# Connect.net
KiCad netlist of a schematic drawn in Altium Designer
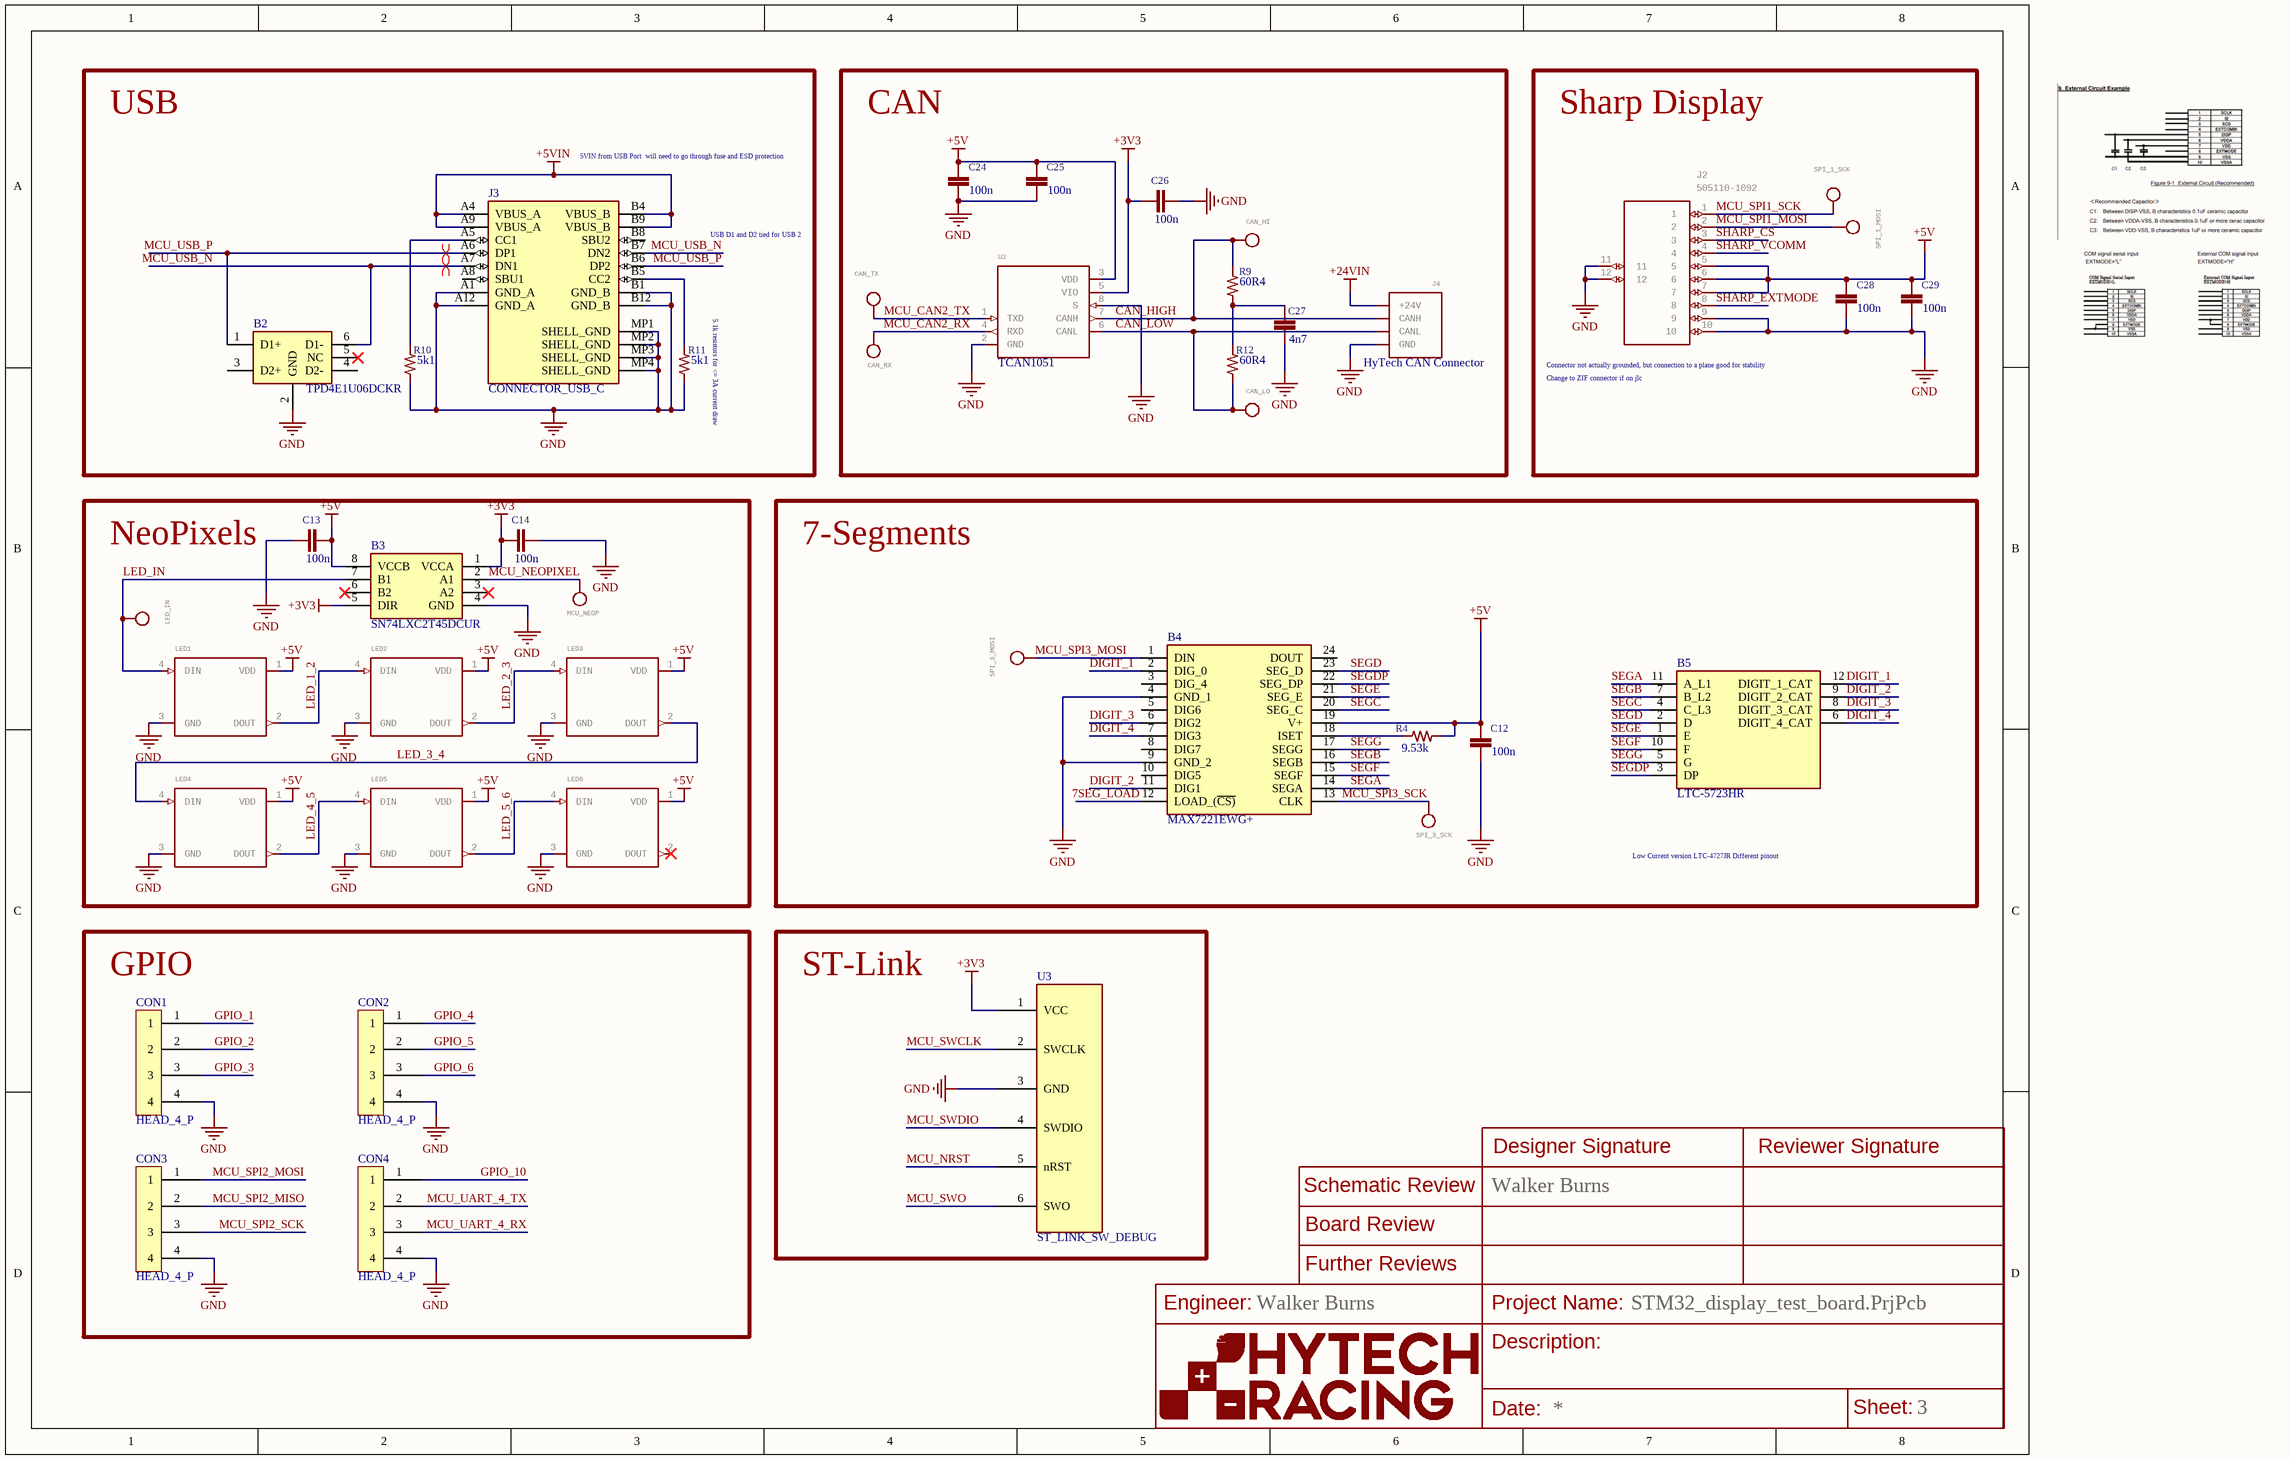
[diagram p0: Connect.SchDoc]

(export (version "E")
  (design (tool "Eeschema 10.0.6"))
  (components
    (comp (ref "B2")
      (value "TPD4E1U06DCKR")
      (footprint "SC-70-6")
      (description "Quad-Channel High-Speed ESD Protection Device")
      (fields (field (name "MOUSER PART NUMBER") "595-TPD4E1U06DCKR"))
      (libsource (lib "HyTechDevices") (part "TPD4E1U06DCKR"))
    )
    (comp (ref "B3")
      (value "SN74LXC2T45DCUR")
      (footprint "VSSOP-8")
      (fields (field (name "MOUSER PART NUMBER") "595-SN74LXC2T45DCUR"))
      (libsource (lib "HyTechDevices") (part "LEVEL_SHIFTER_3V3_TO_5V"))
    )
    (comp (ref "B4")
      (value "MAX7221EWG+")
      (footprint "SOIC-24")
      (description "MAX7221EWG+, LED Display Driver, 8-Digits 64-Segments, 4  5.5 V, 24-Pin SOIC W")
      (fields (field (name "MOUSER PART NUMBER") "700-MAX7221EWG"))
      (libsource (lib "HyTechDevices") (part "MAX7221EWG+"))
    )
    (comp (ref "B5")
      (value "LTC-5723HR")
      (footprint "7SEGMENT_DISP_12_P_TH")
      (description "LED Displays & Accessories 4 Digit, Red Normal Current, Common  Cathode")
      (fields
        (field (name "MOUSER PART NUMBER") "859-LTC-4627JR")
        (field (name "MANUFACTURER_PART_NUMBER") "LTC-4627JR")
      )
      (libsource (lib "HyTechDevices") (part "LED_7_SEGMENT_4_DIGIT"))
    )
    (comp (ref "C12")
      (value "100n")
      (footprint "0402_CAP")
      (fields
        (field (name "MANUFACTURER") "Yageo")
        (field (name "MPN") "CC0603KRX7R0BB104")
        (field (name "TOLERANCE") "10%")
      )
      (libsource (lib "HyTechDevices") (part "CAPACITOR_?_*0402"))
    )
    (comp (ref "C13")
      (value "100n")
      (footprint "0402_CAP")
      (fields
        (field (name "MANUFACTURER") "Yageo")
        (field (name "MPN") "CC0603KRX7R0BB104")
        (field (name "TOLERANCE") "10%")
      )
      (libsource (lib "") (part "CAPACITOR_?_*0402_1"))
    )
    (comp (ref "C14")
      (value "100n")
      (footprint "0402_CAP")
      (fields
        (field (name "MANUFACTURER") "Yageo")
        (field (name "MPN") "CC0603KRX7R0BB104")
        (field (name "TOLERANCE") "10%")
      )
      (libsource (lib "") (part "CAPACITOR_?_*0402_1"))
    )
    (comp (ref "C24")
      (value "100n")
      (footprint "0402_CAP")
      (fields
        (field (name "MANUFACTURER") "Yageo")
        (field (name "MPN") "CC0603KRX7R0BB104")
        (field (name "TOLERANCE") "10%")
      )
      (libsource (lib "HyTechDevices") (part "CAPACITOR_?_*0402"))
    )
    (comp (ref "C25")
      (value "100n")
      (footprint "0402_CAP")
      (fields
        (field (name "MANUFACTURER") "Yageo")
        (field (name "MPN") "CC0603KRX7R0BB104")
        (field (name "TOLERANCE") "10%")
      )
      (libsource (lib "HyTechDevices") (part "CAPACITOR_?_*0402"))
    )
    (comp (ref "C26")
      (value "100n")
      (footprint "0402_CAP")
      (fields
        (field (name "MANUFACTURER") "Yageo")
        (field (name "MPN") "CC0603KRX7R0BB104")
        (field (name "TOLERANCE") "10%")
      )
      (libsource (lib "") (part "CAPACITOR_?_*0402_1"))
    )
    (comp (ref "C27")
      (value "4n7")
      (footprint "0603-CAP")
      (fields
        (field (name "MANUFACTURER") "Yageo")
        (field (name "MPN") "CC0603KRX7R0BB104")
        (field (name "TOLERANCE") "10%")
      )
      (libsource (lib "HyTechDevices") (part "CAPACITOR_?_*0603"))
    )
    (comp (ref "C28")
      (value "100n")
      (footprint "0402_CAP")
      (fields
        (field (name "MANUFACTURER") "Yageo")
        (field (name "MPN") "CC0603KRX7R0BB104")
        (field (name "TOLERANCE") "10%")
      )
      (libsource (lib "HyTechDevices") (part "CAPACITOR_?_*0402"))
    )
    (comp (ref "C29")
      (value "100n")
      (footprint "0402_CAP")
      (fields
        (field (name "MANUFACTURER") "Yageo")
        (field (name "MPN") "CC0603KRX7R0BB104")
        (field (name "TOLERANCE") "10%")
      )
      (libsource (lib "HyTechDevices") (part "CAPACITOR_?_*0402"))
    )
    (comp (ref "CAN_HI")
      (value "Test Point for Probing")
      (footprint "5015")
      (fields (field (name "MANUFACTURER") "Keystone Electronics") (field (name "MPN") "5015"))
      (libsource (lib "HyTechDevices") (part "TEST_POINT"))
    )
    (comp (ref "CAN_LO")
      (value "Test Point for Probing")
      (footprint "5015")
      (fields (field (name "MANUFACTURER") "Keystone Electronics") (field (name "MPN") "5015"))
      (libsource (lib "HyTechDevices") (part "TEST_POINT"))
    )
    (comp (ref "CAN_RX")
      (value "Test Point for Probing")
      (footprint "5015")
      (fields (field (name "MANUFACTURER") "Keystone Electronics") (field (name "MPN") "5015"))
      (libsource (lib "HyTechDevices") (part "TEST_POINT"))
    )
    (comp (ref "CAN_TX")
      (value "Test Point for Probing")
      (footprint "5015")
      (fields (field (name "MANUFACTURER") "Keystone Electronics") (field (name "MPN") "5015"))
      (libsource (lib "HyTechDevices") (part "TEST_POINT"))
    )
    (comp (ref "CON1")
      (value "HEAD_4_P")
      (footprint "1X04")
      (description "4 Pin Standard Header")
      (libsource (lib "HyTechDevices") (part "CONNECTOR_HEADER_4"))
    )
    (comp (ref "CON2")
      (value "HEAD_4_P")
      (footprint "1X04")
      (description "4 Pin Standard Header")
      (libsource (lib "HyTechDevices") (part "CONNECTOR_HEADER_4"))
    )
    (comp (ref "CON3")
      (value "HEAD_4_P")
      (footprint "1X04")
      (description "4 Pin Standard Header")
      (libsource (lib "HyTechDevices") (part "CONNECTOR_HEADER_4"))
    )
    (comp (ref "CON4")
      (value "HEAD_4_P")
      (footprint "1X04")
      (description "4 Pin Standard Header")
      (libsource (lib "HyTechDevices") (part "CONNECTOR_HEADER_4"))
    )
    (comp (ref "FRAME3")
      (value "HyTech Racing Frame (ANSI Size A)  Prints on US Letter Landscape 8.5\" by 11\"   Fill Engineer/Description Fields with Text using the following settings:  Size: 0.1  Ratio: 8%  Line Distance: 50%  Font: Proportional  Layer: 94 Symbol")
      (fields (field (name "LIBRARYNAME") "HyTechFrames"))
      (libsource (lib "HyTechFrames") (part "FRAME"))
    )
    (comp (ref "J2")
      (value "505110-1092")
      (footprint "MOLEX_FPC_CLAMSHELL_10")
      (fields (field (name "MOUSER_PART_NUMBER") "538-505110-1092"))
      (libsource (lib "HyTechDevices") (part "CONNECTOR-10_MOLEX_FPC_CLAMSHELL"))
    )
    (comp (ref "J3")
      (value "CONNECTOR_USB_C")
      (footprint "USB4110GFA")
      (description "USB4110-GF-A\r\nGCT USB C Connector")
      (fields (field (name "MF") "Valcon") (field (name "MP") "CSP-USC16-TR"))
      (libsource (lib "HyTechDevices") (part "CONNECTOR_USB_C"))
    )
    (comp (ref "J4")
      (value "HyTech CAN Connector")
      (footprint "MOLEX_MICROFIT_SMD_RIGHTANGLE_04_DUAL")
      (fields (field (name "MANUFACTURER") "Molex") (field (name "MPN") "0430450411"))
      (libsource (lib "HyTechDevices") (part "CONNECTOR-CAN_?_*μF_S_RA"))
    )
    (comp (ref "LED1")
      (value "IN-PI55QATPRPGPBPW-40  Neopixel RGBW LED  Datasheet")
      (footprint "NEOPIXEL")
      (fields (field (name "MANUFACTURER") "Inolux") (field (name "MPN") "IN-PI55QATPRPGPBPW-40"))
      (libsource (lib "HyTechDevices") (part "NEOPIXEL_*IN-PI55QATPRPGPBPW-40"))
    )
    (comp (ref "LED2")
      (value "IN-PI55QATPRPGPBPW-40  Neopixel RGBW LED  Datasheet")
      (footprint "NEOPIXEL")
      (fields (field (name "MANUFACTURER") "Inolux") (field (name "MPN") "IN-PI55QATPRPGPBPW-40"))
      (libsource (lib "HyTechDevices") (part "NEOPIXEL_*IN-PI55QATPRPGPBPW-40"))
    )
    (comp (ref "LED3")
      (value "IN-PI55QATPRPGPBPW-40  Neopixel RGBW LED  Datasheet")
      (footprint "NEOPIXEL")
      (fields (field (name "MANUFACTURER") "Inolux") (field (name "MPN") "IN-PI55QATPRPGPBPW-40"))
      (libsource (lib "HyTechDevices") (part "NEOPIXEL_*IN-PI55QATPRPGPBPW-40"))
    )
    (comp (ref "LED4")
      (value "IN-PI55QATPRPGPBPW-40  Neopixel RGBW LED  Datasheet")
      (footprint "NEOPIXEL")
      (fields (field (name "MANUFACTURER") "Inolux") (field (name "MPN") "IN-PI55QATPRPGPBPW-40"))
      (libsource (lib "HyTechDevices") (part "NEOPIXEL_*IN-PI55QATPRPGPBPW-40"))
    )
    (comp (ref "LED5")
      (value "IN-PI55QATPRPGPBPW-40  Neopixel RGBW LED  Datasheet")
      (footprint "NEOPIXEL")
      (fields (field (name "MANUFACTURER") "Inolux") (field (name "MPN") "IN-PI55QATPRPGPBPW-40"))
      (libsource (lib "HyTechDevices") (part "NEOPIXEL_*IN-PI55QATPRPGPBPW-40"))
    )
    (comp (ref "LED6")
      (value "IN-PI55QATPRPGPBPW-40  Neopixel RGBW LED  Datasheet")
      (footprint "NEOPIXEL")
      (fields (field (name "MANUFACTURER") "Inolux") (field (name "MPN") "IN-PI55QATPRPGPBPW-40"))
      (libsource (lib "HyTechDevices") (part "NEOPIXEL_*IN-PI55QATPRPGPBPW-40"))
    )
    (comp (ref "LED_IN")
      (value "Test Point for Probing")
      (footprint "5015")
      (fields (field (name "MANUFACTURER") "Keystone Electronics") (field (name "MPN") "5015"))
      (libsource (lib "HyTechDevices") (part "TEST_POINT"))
    )
    (comp (ref "MCU_NEOP")
      (value "Test Point for Probing")
      (footprint "5015")
      (fields (field (name "MANUFACTURER") "Keystone Electronics") (field (name "MPN") "5015"))
      (libsource (lib "HyTechDevices") (part "TEST_POINT"))
    )
    (comp (ref "R4")
      (value "9.53k")
      (footprint "0603-RES")
      (fields
        (field (name "MANUFACTURER") "Yageo")
        (field (name "MPN") "RC0603FR-070RL")
        (field (name "POWER") "0.1W")
      )
      (libsource (lib "") (part "RESISTOR_?_*0603_1"))
    )
    (comp (ref "R9")
      (value "60R4")
      (footprint "0603-RES")
      (fields
        (field (name "MANUFACTURER") "Yageo")
        (field (name "MPN") "RC0603FR-070RL")
        (field (name "POWER") "0.1W")
      )
      (libsource (lib "HyTechDevices") (part "RESISTOR_?_*0603"))
    )
    (comp (ref "R10")
      (value "5k1")
      (footprint "0603-RES")
      (fields
        (field (name "MANUFACTURER") "Yageo")
        (field (name "MPN") "RC0603FR-070RL")
        (field (name "POWER") "0.1W")
      )
      (libsource (lib "HyTechDevices") (part "RESISTOR_?_*0603"))
    )
    (comp (ref "R11")
      (value "5k1")
      (footprint "0603-RES")
      (fields
        (field (name "MANUFACTURER") "Yageo")
        (field (name "MPN") "RC0603FR-070RL")
        (field (name "POWER") "0.1W")
      )
      (libsource (lib "HyTechDevices") (part "RESISTOR_?_*0603"))
    )
    (comp (ref "R12")
      (value "60R4")
      (footprint "0603-RES")
      (fields
        (field (name "MANUFACTURER") "Yageo")
        (field (name "MPN") "RC0603FR-070RL")
        (field (name "POWER") "0.1W")
      )
      (libsource (lib "HyTechDevices") (part "RESISTOR_?_*0603"))
    )
    (comp (ref "SPI_1_MOSI")
      (value "Test Point for Probing")
      (footprint "5015")
      (fields (field (name "MANUFACTURER") "Keystone Electronics") (field (name "MPN") "5015"))
      (libsource (lib "HyTechDevices") (part "TEST_POINT"))
    )
    (comp (ref "SPI_1_SCK")
      (value "Test Point for Probing")
      (footprint "5015")
      (fields (field (name "MANUFACTURER") "Keystone Electronics") (field (name "MPN") "5015"))
      (libsource (lib "HyTechDevices") (part "TEST_POINT"))
    )
    (comp (ref "SPI_3_MOSI")
      (value "Test Point for Probing")
      (footprint "5015")
      (fields (field (name "MANUFACTURER") "Keystone Electronics") (field (name "MPN") "5015"))
      (libsource (lib "HyTechDevices") (part "TEST_POINT"))
    )
    (comp (ref "SPI_3_SCK")
      (value "Test Point for Probing")
      (footprint "5015")
      (fields (field (name "MANUFACTURER") "Keystone Electronics") (field (name "MPN") "5015"))
      (libsource (lib "HyTechDevices") (part "TEST_POINT"))
    )
    (comp (ref "U2")
      (value "TCAN1051")
      (footprint "SOIC-08(NARROW,0-15\")")
      (fields (field (name "MANUFACTURER") "Texas Instruments") (field (name "MPN") "TCAN1051HGVDRQ1"))
      (libsource (lib "HyTechDevices") (part "TCAN1051*V-Q1"))
    )
    (comp (ref "U3")
      (value "ST_LINK_SW_DEBUG")
      (footprint "HEADER_6_P")
      (libsource (lib "HyTechDevices") (part "CONNECTOR_ST_LINK"))
    )
  )
  (nets
    (net (code "1") (name "+3V3") (class "Default")
      (node (ref "B3") (pin "1") (pinfunction "VCCA_1") (pintype "passive"))
      (node (ref "B3") (pin "5") (pinfunction "DIR_5") (pintype "passive"))
      (node (ref "C14") (pin "2") (pinfunction "2_2") (pintype "passive"))
      (node (ref "C26") (pin "2") (pinfunction "2_2") (pintype "passive"))
      (node (ref "U2") (pin "5") (pinfunction "VIO_5") (pintype "power_in"))
      (node (ref "U3") (pin "1") (pinfunction "VCC_1") (pintype "passive"))
    )
    (net (code "2") (name "+5V") (class "Default")
      (node (ref "B3") (pin "8") (pinfunction "VCCB_8") (pintype "passive"))
      (node (ref "B4") (pin "19") (pinfunction "V+_19") (pintype "passive"))
      (node (ref "C12") (pin "2") (pinfunction "2_2") (pintype "passive"))
      (node (ref "C13") (pin "1") (pinfunction "1_1") (pintype "passive"))
      (node (ref "C24") (pin "2") (pinfunction "2_2") (pintype "passive"))
      (node (ref "C25") (pin "2") (pinfunction "2_2") (pintype "passive"))
      (node (ref "C28") (pin "2") (pinfunction "2_2") (pintype "passive"))
      (node (ref "C29") (pin "2") (pinfunction "2_2") (pintype "passive"))
      (node (ref "J2") (pin "5") (pinfunction "5_5") (pintype "bidirectional"))
      (node (ref "J2") (pin "6") (pinfunction "6_6") (pintype "bidirectional"))
      (node (ref "J2") (pin "7") (pinfunction "7_7") (pintype "bidirectional"))
      (node (ref "LED1") (pin "1") (pinfunction "VDD_1") (pintype "power_in"))
      (node (ref "LED2") (pin "1") (pinfunction "VDD_1") (pintype "power_in"))
      (node (ref "LED3") (pin "1") (pinfunction "VDD_1") (pintype "power_in"))
      (node (ref "LED4") (pin "1") (pinfunction "VDD_1") (pintype "power_in"))
      (node (ref "LED5") (pin "1") (pinfunction "VDD_1") (pintype "power_in"))
      (node (ref "LED6") (pin "1") (pinfunction "VDD_1") (pintype "power_in"))
      (node (ref "R4") (pin "2") (pinfunction "2_2") (pintype "passive"))
      (node (ref "U2") (pin "3") (pinfunction "VDD_3") (pintype "power_in"))
    )
    (net (code "3") (name "+5VIN") (class "Default")
      (node (ref "J3") (pin "A4") (pinfunction "VBUS_A_A4") (pintype "power_in"))
      (node (ref "J3") (pin "A9") (pinfunction "VBUS_A_A9") (pintype "power_in"))
      (node (ref "J3") (pin "B4") (pinfunction "VBUS_B_B4") (pintype "power_in"))
      (node (ref "J3") (pin "B9") (pinfunction "VBUS_B_B9") (pintype "power_in"))
    )
    (net (code "4") (name "+24VIN") (class "Default")
      (node (ref "J4") (pin "1") (pinfunction "+24V_1") (pintype "power_in"))
    )
    (net (code "5") (name "/7SEG_LOAD") (class "Default")
      (node (ref "B4") (pin "12") (pinfunction "LOAD_(~{CS)}_12") (pintype "passive"))
    )
    (net (code "6") (name "/CAN_HIGH") (class "Default")
      (node (ref "CAN_HI") (pin "1") (pinfunction "1_1") (pintype "passive"))
      (node (ref "J4") (pin "4") (pinfunction "CANH_4") (pintype "bidirectional"))
      (node (ref "R9") (pin "1") (pinfunction "1_1") (pintype "passive"))
      (node (ref "U2") (pin "7") (pinfunction "CANH_7") (pintype "output"))
    )
    (net (code "7") (name "/CAN_LOW") (class "Default")
      (node (ref "CAN_LO") (pin "1") (pinfunction "1_1") (pintype "passive"))
      (node (ref "J4") (pin "3") (pinfunction "CANL_3") (pintype "bidirectional"))
      (node (ref "R12") (pin "2") (pinfunction "2_2") (pintype "passive"))
      (node (ref "U2") (pin "6") (pinfunction "CANL_6") (pintype "bidirectional"))
    )
    (net (code "8") (name "/DIGIT_1") (class "Default")
      (node (ref "B4") (pin "2") (pinfunction "DIG_0_2") (pintype "passive"))
      (node (ref "B5") (pin "12") (pinfunction "DIGIT_1_CAT_12") (pintype "passive"))
    )
    (net (code "9") (name "/DIGIT_2") (class "Default")
      (node (ref "B4") (pin "11") (pinfunction "DIG1_11") (pintype "passive"))
      (node (ref "B5") (pin "9") (pinfunction "DIGIT_2_CAT_9") (pintype "passive"))
    )
    (net (code "10") (name "/DIGIT_3") (class "Default")
      (node (ref "B4") (pin "6") (pinfunction "DIG2_6") (pintype "passive"))
      (node (ref "B5") (pin "8") (pinfunction "DIGIT_3_CAT_8") (pintype "passive"))
    )
    (net (code "11") (name "/DIGIT_4") (class "Default")
      (node (ref "B4") (pin "7") (pinfunction "DIG3_7") (pintype "passive"))
      (node (ref "B5") (pin "6") (pinfunction "DIGIT_4_CAT_6") (pintype "passive"))
    )
    (net (code "12") (name "/GPIO_1") (class "Default")
      (node (ref "CON1") (pin "1") (pinfunction "1_1") (pintype "passive"))
    )
    (net (code "13") (name "/GPIO_2") (class "Default")
      (node (ref "CON1") (pin "2") (pinfunction "2_2") (pintype "passive"))
    )
    (net (code "14") (name "/GPIO_3") (class "Default")
      (node (ref "CON1") (pin "3") (pinfunction "3_3") (pintype "passive"))
    )
    (net (code "15") (name "/GPIO_4") (class "Default")
      (node (ref "CON2") (pin "1") (pinfunction "1_1") (pintype "passive"))
    )
    (net (code "16") (name "/GPIO_5") (class "Default")
      (node (ref "CON2") (pin "2") (pinfunction "2_2") (pintype "passive"))
    )
    (net (code "17") (name "/GPIO_6") (class "Default")
      (node (ref "CON2") (pin "3") (pinfunction "3_3") (pintype "passive"))
    )
    (net (code "18") (name "/GPIO_10") (class "Default")
      (node (ref "CON4") (pin "1") (pinfunction "1_1") (pintype "passive"))
    )
    (net (code "19") (name "/LED_1_2") (class "Default")
      (node (ref "LED1") (pin "2") (pinfunction "DOUT_2") (pintype "output"))
      (node (ref "LED2") (pin "4") (pinfunction "DIN_4") (pintype "input"))
    )
    (net (code "20") (name "/LED_2_3") (class "Default")
      (node (ref "LED2") (pin "2") (pinfunction "DOUT_2") (pintype "output"))
      (node (ref "LED3") (pin "4") (pinfunction "DIN_4") (pintype "input"))
    )
    (net (code "21") (name "/LED_3_4") (class "Default")
      (node (ref "LED3") (pin "2") (pinfunction "DOUT_2") (pintype "output"))
      (node (ref "LED4") (pin "4") (pinfunction "DIN_4") (pintype "input"))
    )
    (net (code "22") (name "/LED_4_5") (class "Default")
      (node (ref "LED4") (pin "2") (pinfunction "DOUT_2") (pintype "output"))
      (node (ref "LED5") (pin "4") (pinfunction "DIN_4") (pintype "input"))
    )
    (net (code "23") (name "/LED_5_6") (class "Default")
      (node (ref "LED5") (pin "2") (pinfunction "DOUT_2") (pintype "output"))
      (node (ref "LED6") (pin "4") (pinfunction "DIN_4") (pintype "input"))
    )
    (net (code "24") (name "/LED_IN") (class "Default")
      (node (ref "B3") (pin "7") (pinfunction "B1_7") (pintype "passive"))
      (node (ref "LED1") (pin "4") (pinfunction "DIN_4") (pintype "input"))
      (node (ref "LED_IN") (pin "1") (pinfunction "1_1") (pintype "passive"))
    )
    (net (code "25") (name "/MCU_CAN2_RX") (class "Default")
      (node (ref "CAN_RX") (pin "1") (pinfunction "1_1") (pintype "passive"))
      (node (ref "U2") (pin "4") (pinfunction "RXD_4") (pintype "output"))
    )
    (net (code "26") (name "/MCU_CAN2_TX") (class "Default")
      (node (ref "CAN_TX") (pin "1") (pinfunction "1_1") (pintype "passive"))
      (node (ref "U2") (pin "1") (pinfunction "TXD_1") (pintype "input"))
    )
    (net (code "27") (name "/MCU_NEOPIXEL") (class "Default")
      (node (ref "B3") (pin "2") (pinfunction "A1_2") (pintype "passive"))
      (node (ref "MCU_NEOP") (pin "1") (pinfunction "1_1") (pintype "passive"))
    )
    (net (code "28") (name "/MCU_NRST") (class "Default")
      (node (ref "U3") (pin "5") (pinfunction "nRST_5") (pintype "passive"))
    )
    (net (code "29") (name "/MCU_SPI1_MOSI") (class "Default")
      (node (ref "J2") (pin "2") (pinfunction "2_2") (pintype "bidirectional"))
      (node (ref "SPI_1_MOSI") (pin "1") (pinfunction "1_1") (pintype "passive"))
    )
    (net (code "30") (name "/MCU_SPI1_SCK") (class "Default")
      (node (ref "J2") (pin "1") (pinfunction "1_1") (pintype "bidirectional"))
      (node (ref "SPI_1_SCK") (pin "1") (pinfunction "1_1") (pintype "passive"))
    )
    (net (code "31") (name "/MCU_SPI2_MISO") (class "Default")
      (node (ref "CON3") (pin "2") (pinfunction "2_2") (pintype "passive"))
    )
    (net (code "32") (name "/MCU_SPI2_MOSI") (class "Default")
      (node (ref "CON3") (pin "1") (pinfunction "1_1") (pintype "passive"))
    )
    (net (code "33") (name "/MCU_SPI2_SCK") (class "Default")
      (node (ref "CON3") (pin "3") (pinfunction "3_3") (pintype "passive"))
    )
    (net (code "34") (name "/MCU_SPI3_MOSI") (class "Default")
      (node (ref "B4") (pin "1") (pinfunction "DIN_1") (pintype "passive"))
      (node (ref "SPI_3_MOSI") (pin "1") (pinfunction "1_1") (pintype "passive"))
    )
    (net (code "35") (name "/MCU_SPI3_SCK") (class "Default")
      (node (ref "B4") (pin "13") (pinfunction "CLK_13") (pintype "passive"))
      (node (ref "SPI_3_SCK") (pin "1") (pinfunction "1_1") (pintype "passive"))
    )
    (net (code "36") (name "/MCU_SWCLK") (class "Default")
      (node (ref "U3") (pin "2") (pinfunction "SWCLK_2") (pintype "passive"))
    )
    (net (code "37") (name "/MCU_SWDIO") (class "Default")
      (node (ref "U3") (pin "4") (pinfunction "SWDIO_4") (pintype "passive"))
    )
    (net (code "38") (name "/MCU_SWO") (class "Default")
      (node (ref "U3") (pin "6") (pinfunction "SWO_6") (pintype "passive"))
    )
    (net (code "39") (name "/MCU_UART_4_RX") (class "Default")
      (node (ref "CON4") (pin "3") (pinfunction "3_3") (pintype "passive"))
    )
    (net (code "40") (name "/MCU_UART_4_TX") (class "Default")
      (node (ref "CON4") (pin "2") (pinfunction "2_2") (pintype "passive"))
    )
    (net (code "41") (name "/MCU_USB_N") (class "Default")
      (node (ref "B2") (pin "6") (pinfunction "D1-_6") (pintype "passive"))
      (node (ref "J3") (pin "A7") (pinfunction "DN1_A7") (pintype "bidirectional"))
      (node (ref "J3") (pin "B7") (pinfunction "DN2_B7") (pintype "bidirectional"))
    )
    (net (code "42") (name "/MCU_USB_P") (class "Default")
      (node (ref "B2") (pin "1") (pinfunction "D1+_1") (pintype "passive"))
      (node (ref "J3") (pin "A6") (pinfunction "DP1_A6") (pintype "bidirectional"))
      (node (ref "J3") (pin "B6") (pinfunction "DP2_B6") (pintype "bidirectional"))
    )
    (net (code "43") (name "/SEGA") (class "Default")
      (node (ref "B4") (pin "14") (pinfunction "SEGA_14") (pintype "passive"))
      (node (ref "B5") (pin "11") (pinfunction "A_L1_11") (pintype "passive"))
    )
    (net (code "44") (name "/SEGB") (class "Default")
      (node (ref "B4") (pin "16") (pinfunction "SEGB_16") (pintype "passive"))
      (node (ref "B5") (pin "7") (pinfunction "B_L2_7") (pintype "passive"))
    )
    (net (code "45") (name "/SEGC") (class "Default")
      (node (ref "B4") (pin "20") (pinfunction "SEG_C_20") (pintype "passive"))
      (node (ref "B5") (pin "4") (pinfunction "C_L3_4") (pintype "passive"))
    )
    (net (code "46") (name "/SEGD") (class "Default")
      (node (ref "B4") (pin "23") (pinfunction "SEG_D_23") (pintype "passive"))
      (node (ref "B5") (pin "2") (pinfunction "D_2") (pintype "passive"))
    )
    (net (code "47") (name "/SEGDP") (class "Default")
      (node (ref "B4") (pin "22") (pinfunction "SEG_DP_22") (pintype "passive"))
      (node (ref "B5") (pin "3") (pinfunction "DP_3") (pintype "passive"))
    )
    (net (code "48") (name "/SEGE") (class "Default")
      (node (ref "B4") (pin "21") (pinfunction "SEG_E_21") (pintype "passive"))
      (node (ref "B5") (pin "1") (pinfunction "E_1") (pintype "passive"))
    )
    (net (code "49") (name "/SEGF") (class "Default")
      (node (ref "B4") (pin "15") (pinfunction "SEGF_15") (pintype "passive"))
      (node (ref "B5") (pin "10") (pinfunction "F_10") (pintype "passive"))
    )
    (net (code "50") (name "/SEGG") (class "Default")
      (node (ref "B4") (pin "17") (pinfunction "SEGG_17") (pintype "passive"))
      (node (ref "B5") (pin "5") (pinfunction "G_5") (pintype "passive"))
    )
    (net (code "51") (name "/SHARP_CS") (class "Default")
      (node (ref "J2") (pin "3") (pinfunction "3_3") (pintype "bidirectional"))
    )
    (net (code "52") (name "/SHARP_EXTMODE") (class "Default")
      (node (ref "J2") (pin "8") (pinfunction "8_8") (pintype "bidirectional"))
    )
    (net (code "53") (name "/SHARP_VCOMM") (class "Default")
      (node (ref "J2") (pin "4") (pinfunction "4_4") (pintype "bidirectional"))
    )
    (net (code "54") (name "GND") (class "Default")
      (node (ref "B2") (pin "2") (pinfunction "GND_2") (pintype "passive"))
      (node (ref "B3") (pin "4") (pinfunction "GND_4") (pintype "passive"))
      (node (ref "B4") (pin "4") (pinfunction "GND_1_4") (pintype "passive"))
      (node (ref "B4") (pin "9") (pinfunction "GND_2_9") (pintype "passive"))
      (node (ref "C12") (pin "1") (pinfunction "1_1") (pintype "passive"))
      (node (ref "C13") (pin "2") (pinfunction "2_2") (pintype "passive"))
      (node (ref "C14") (pin "1") (pinfunction "1_1") (pintype "passive"))
      (node (ref "C24") (pin "1") (pinfunction "1_1") (pintype "passive"))
      (node (ref "C25") (pin "1") (pinfunction "1_1") (pintype "passive"))
      (node (ref "C26") (pin "1") (pinfunction "1_1") (pintype "passive"))
      (node (ref "C27") (pin "1") (pinfunction "1_1") (pintype "passive"))
      (node (ref "C28") (pin "1") (pinfunction "1_1") (pintype "passive"))
      (node (ref "C29") (pin "1") (pinfunction "1_1") (pintype "passive"))
      (node (ref "CON1") (pin "4") (pinfunction "4_4") (pintype "passive"))
      (node (ref "CON2") (pin "4") (pinfunction "4_4") (pintype "passive"))
      (node (ref "CON3") (pin "4") (pinfunction "4_4") (pintype "passive"))
      (node (ref "CON4") (pin "4") (pinfunction "4_4") (pintype "passive"))
      (node (ref "J2") (pin "10") (pinfunction "10_10") (pintype "bidirectional"))
      (node (ref "J2") (pin "11") (pinfunction "11_11") (pintype "bidirectional"))
      (node (ref "J2") (pin "12") (pinfunction "12_12") (pintype "bidirectional"))
      (node (ref "J2") (pin "9") (pinfunction "9_9") (pintype "bidirectional"))
      (node (ref "J3") (pin "A1") (pinfunction "GND_A_A1") (pintype "power_in"))
      (node (ref "J3") (pin "A12") (pinfunction "GND_A_A12") (pintype "power_in"))
      (node (ref "J3") (pin "B1") (pinfunction "GND_B_B1") (pintype "power_in"))
      (node (ref "J3") (pin "B12") (pinfunction "GND_B_B12") (pintype "power_in"))
      (node (ref "J3") (pin "MP1") (pinfunction "SHELL_GND_MP1") (pintype "power_in"))
      (node (ref "J3") (pin "MP2") (pinfunction "SHELL_GND_MP2") (pintype "power_in"))
      (node (ref "J3") (pin "MP3") (pinfunction "SHELL_GND_MP3") (pintype "power_in"))
      (node (ref "J3") (pin "MP4") (pinfunction "SHELL_GND_MP4") (pintype "power_in"))
      (node (ref "J4") (pin "2") (pinfunction "GND_2") (pintype "power_in"))
      (node (ref "LED1") (pin "3") (pinfunction "GND_3") (pintype "power_in"))
      (node (ref "LED2") (pin "3") (pinfunction "GND_3") (pintype "power_in"))
      (node (ref "LED3") (pin "3") (pinfunction "GND_3") (pintype "power_in"))
      (node (ref "LED4") (pin "3") (pinfunction "GND_3") (pintype "power_in"))
      (node (ref "LED5") (pin "3") (pinfunction "GND_3") (pintype "power_in"))
      (node (ref "LED6") (pin "3") (pinfunction "GND_3") (pintype "power_in"))
      (node (ref "R10") (pin "2") (pinfunction "2_2") (pintype "passive"))
      (node (ref "R11") (pin "2") (pinfunction "2_2") (pintype "passive"))
      (node (ref "U2") (pin "2") (pinfunction "GND_2") (pintype "power_in"))
      (node (ref "U2") (pin "8") (pinfunction "S_8") (pintype "input"))
      (node (ref "U3") (pin "3") (pinfunction "GND_3") (pintype "passive"))
    )
    (net (code "55") (name "Net-(B4-ISET)") (class "Default")
      (node (ref "B4") (pin "18") (pinfunction "ISET_18") (pintype "passive"))
      (node (ref "R4") (pin "1") (pinfunction "1_1") (pintype "passive"))
    )
    (net (code "56") (name "Net-(C27-Pad2)") (class "Default")
      (node (ref "C27") (pin "2") (pinfunction "2_2") (pintype "passive"))
      (node (ref "R12") (pin "1") (pinfunction "1_1") (pintype "passive"))
      (node (ref "R9") (pin "2") (pinfunction "2_2") (pintype "passive"))
    )
    (net (code "57") (name "Net-(J3-CC1)") (class "Default")
      (node (ref "J3") (pin "A5") (pinfunction "CC1_A5") (pintype "bidirectional"))
      (node (ref "R10") (pin "1") (pinfunction "1_1") (pintype "passive"))
    )
    (net (code "58") (name "Net-(J3-CC2)") (class "Default")
      (node (ref "J3") (pin "B5") (pinfunction "CC2_B5") (pintype "bidirectional"))
      (node (ref "R11") (pin "1") (pinfunction "1_1") (pintype "passive"))
    )
    (net (code "59") (name "unconnected-(B2-D2+-Pad3)") (class "Default")
      (node (ref "B2") (pin "3") (pinfunction "D2+_3") (pintype "passive"))
    )
    (net (code "60") (name "unconnected-(B2-D2--Pad4)") (class "Default")
      (node (ref "B2") (pin "4") (pinfunction "D2-_4") (pintype "passive"))
    )
    (net (code "61") (name "unconnected-(B2-NC-Pad5)") (class "Default")
      (node (ref "B2") (pin "5") (pinfunction "NC_5") (pintype "passive+no_connect"))
    )
    (net (code "62") (name "unconnected-(B3-A2-Pad3)") (class "Default")
      (node (ref "B3") (pin "3") (pinfunction "A2_3") (pintype "passive+no_connect"))
    )
    (net (code "63") (name "unconnected-(B3-B2-Pad6)") (class "Default")
      (node (ref "B3") (pin "6") (pinfunction "B2_6") (pintype "passive+no_connect"))
    )
    (net (code "64") (name "unconnected-(B4-DIG5-Pad10)") (class "Default")
      (node (ref "B4") (pin "10") (pinfunction "DIG5_10") (pintype "passive"))
    )
    (net (code "65") (name "unconnected-(B4-DIG6-Pad5)") (class "Default")
      (node (ref "B4") (pin "5") (pinfunction "DIG6_5") (pintype "passive"))
    )
    (net (code "66") (name "unconnected-(B4-DIG7-Pad8)") (class "Default")
      (node (ref "B4") (pin "8") (pinfunction "DIG7_8") (pintype "passive"))
    )
    (net (code "67") (name "unconnected-(B4-DIG_4-Pad3)") (class "Default")
      (node (ref "B4") (pin "3") (pinfunction "DIG_4_3") (pintype "passive"))
    )
    (net (code "68") (name "unconnected-(B4-DOUT-Pad24)") (class "Default")
      (node (ref "B4") (pin "24") (pinfunction "DOUT_24") (pintype "passive"))
    )
    (net (code "69") (name "unconnected-(J3-SBU1-PadA8)") (class "Default")
      (node (ref "J3") (pin "A8") (pinfunction "SBU1_A8") (pintype "bidirectional"))
    )
    (net (code "70") (name "unconnected-(J3-SBU2-PadB8)") (class "Default")
      (node (ref "J3") (pin "B8") (pinfunction "SBU2_B8") (pintype "bidirectional"))
    )
    (net (code "71") (name "unconnected-(LED6-DOUT-Pad2)") (class "Default")
      (node (ref "LED6") (pin "2") (pinfunction "DOUT_2") (pintype "output+no_connect"))
    )
  )
)
